# controller.net
KiCad netlist of a schematic drawn in Altium Designer
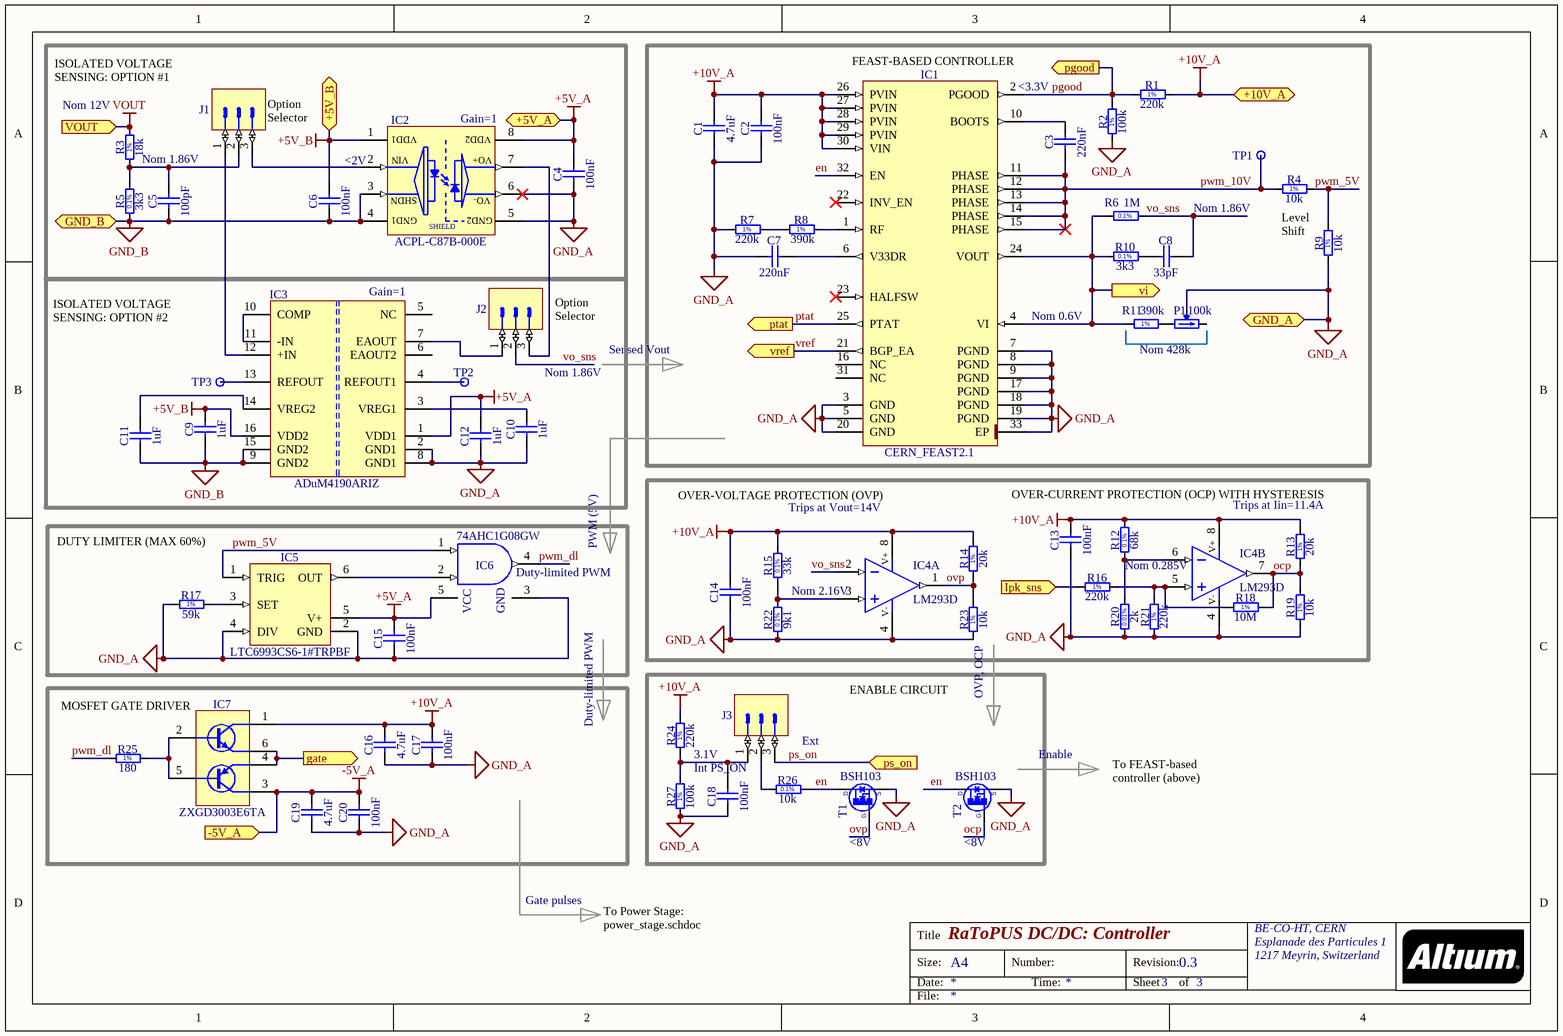
[diagram p0: controller.schdoc]

(export (version "E")
  (design (tool "Eeschema 10.0.6"))
  (components
    (comp (ref "C1")
      (value "4.7uF")
      (footprint "CAPC2012X135N")
      (description "Non-polarised capacitor")
      (fields
        (field (name "PART NUMBER") "CC0805_4.7UF_16V_10%_X7R")
        (field (name "VOLTAGE") "16V")
        (field (name "AUTHOR") "CERN DEM JLC")
      )
      (libsource (lib "Capacitors") (part "Capacitor - non polarized"))
    )
    (comp (ref "C2")
      (value "100nF")
      (footprint "CAPC2012X135N")
      (description "Non-polarised capacitor")
      (fields
        (field (name "PART NUMBER") "CC0805_100NF_50V_10%_X7R")
        (field (name "VOLTAGE") "50V")
        (field (name "AUTHOR") "CERN DEM JLC")
      )
      (libsource (lib "Capacitors") (part "Capacitor - non polarized"))
    )
    (comp (ref "C3")
      (value "220nF")
      (footprint "CAPC2012X135N")
      (description "Non-polarised capacitor")
      (fields
        (field (name "PART NUMBER") "CC0805_220NF_50V_10%_X7R")
        (field (name "VOLTAGE") "50V")
        (field (name "AUTHOR") "CERN DEM JLC")
      )
      (libsource (lib "Capacitors") (part "Capacitor - non polarized"))
    )
    (comp (ref "C4")
      (value "100nF")
      (footprint "CAPC2012X135N")
      (description "Non-polarised capacitor")
      (fields
        (field (name "PART NUMBER") "CC0805_100NF_50V_10%_X7R")
        (field (name "VOLTAGE") "50V")
        (field (name "AUTHOR") "CERN DEM JLC")
      )
      (libsource (lib "Capacitors") (part "Capacitor - non polarized"))
    )
    (comp (ref "C5")
      (value "100pF")
      (footprint "CAPC2012X88N")
      (description "Non-polarised capacitor")
      (fields
        (field (name "PART NUMBER") "CC0805_100PF_50V_5%_C0G_KEMET_C0805C101J5GACAUTO")
        (field (name "VOLTAGE") "50V")
        (field (name "AUTHOR") "CERN DEM BC")
      )
      (libsource (lib "Capacitors") (part "Capacitor - non polarized"))
    )
    (comp (ref "C6")
      (value "100nF")
      (footprint "CAPC2012X135N")
      (description "Non-polarised capacitor")
      (fields
        (field (name "PART NUMBER") "CC0805_100NF_50V_10%_X7R")
        (field (name "VOLTAGE") "50V")
        (field (name "AUTHOR") "CERN DEM JLC")
      )
      (libsource (lib "Capacitors") (part "Capacitor - non polarized"))
    )
    (comp (ref "C7")
      (value "220nF")
      (footprint "CAPC2012X135N")
      (description "Non-polarised capacitor")
      (fields
        (field (name "PART NUMBER") "CC0805_220NF_50V_10%_X7R")
        (field (name "VOLTAGE") "50V")
        (field (name "AUTHOR") "CERN DEM JLC")
      )
      (libsource (lib "Capacitors") (part "Capacitor - non polarized"))
    )
    (comp (ref "C8")
      (value "33pF")
      (footprint "CAPC2012X88N")
      (description "Non-polarised capacitor")
      (fields
        (field (name "PART NUMBER") "CC0805_33PF_50V_5%_C0G_KEMET_C0805C330J5GACAUTO")
        (field (name "VOLTAGE") "50V")
        (field (name "AUTHOR") "CERN DEM BC")
      )
      (libsource (lib "Capacitors") (part "Capacitor - non polarized"))
    )
    (comp (ref "C9")
      (value "1uF")
      (footprint "CAPC3216X140N")
      (description "Non-polarised capacitor")
      (fields
        (field (name "PART NUMBER") "CC1206_1UF_50V_10%_X7R")
        (field (name "VOLTAGE") "50V")
        (field (name "AUTHOR") "CERN DEM JLC")
      )
      (libsource (lib "Capacitors") (part "Capacitor - non polarized"))
    )
    (comp (ref "C10")
      (value "1uF")
      (footprint "CAPC3216X140N")
      (description "Non-polarised capacitor")
      (fields
        (field (name "PART NUMBER") "CC1206_1UF_50V_10%_X7R")
        (field (name "VOLTAGE") "50V")
        (field (name "AUTHOR") "CERN DEM JLC")
      )
      (libsource (lib "Capacitors") (part "Capacitor - non polarized"))
    )
    (comp (ref "C11")
      (value "1uF")
      (footprint "CAPC3216X140N")
      (description "Non-polarised capacitor")
      (fields
        (field (name "PART NUMBER") "CC1206_1UF_50V_10%_X7R")
        (field (name "VOLTAGE") "50V")
        (field (name "AUTHOR") "CERN DEM JLC")
      )
      (libsource (lib "Capacitors") (part "Capacitor - non polarized"))
    )
    (comp (ref "C12")
      (value "1uF")
      (footprint "CAPC3216X140N")
      (description "Non-polarised capacitor")
      (fields
        (field (name "PART NUMBER") "CC1206_1UF_50V_10%_X7R")
        (field (name "VOLTAGE") "50V")
        (field (name "AUTHOR") "CERN DEM JLC")
      )
      (libsource (lib "Capacitors") (part "Capacitor - non polarized"))
    )
    (comp (ref "C13")
      (value "100nF")
      (footprint "CAPC2012X135N")
      (description "Non-polarised capacitor")
      (fields
        (field (name "PART NUMBER") "CC0805_100NF_50V_10%_X7R")
        (field (name "VOLTAGE") "50V")
        (field (name "AUTHOR") "CERN DEM JLC")
      )
      (libsource (lib "Capacitors") (part "Capacitor - non polarized"))
    )
    (comp (ref "C14")
      (value "100nF")
      (footprint "CAPC2012X135N")
      (description "Non-polarised capacitor")
      (fields
        (field (name "PART NUMBER") "CC0805_100NF_50V_10%_X7R")
        (field (name "VOLTAGE") "50V")
        (field (name "AUTHOR") "CERN DEM JLC")
      )
      (libsource (lib "Capacitors") (part "Capacitor - non polarized"))
    )
    (comp (ref "C15")
      (value "100nF")
      (footprint "CAPC2012X135N")
      (description "Non-polarised capacitor")
      (fields
        (field (name "PART NUMBER") "CC0805_100NF_50V_10%_X7R")
        (field (name "VOLTAGE") "50V")
        (field (name "AUTHOR") "CERN DEM JLC")
      )
      (libsource (lib "Capacitors") (part "Capacitor - non polarized"))
    )
    (comp (ref "C16")
      (value "4.7uF")
      (footprint "CAPC2012X135N")
      (description "Non-polarised capacitor")
      (fields
        (field (name "PART NUMBER") "CC0805_4.7UF_16V_10%_X7R")
        (field (name "VOLTAGE") "16V")
        (field (name "AUTHOR") "CERN DEM JLC")
      )
      (libsource (lib "Capacitors") (part "Capacitor - non polarized"))
    )
    (comp (ref "C17")
      (value "100nF")
      (footprint "CAPC2012X135N")
      (description "Non-polarised capacitor")
      (fields
        (field (name "PART NUMBER") "CC0805_100NF_50V_10%_X7R")
        (field (name "VOLTAGE") "50V")
        (field (name "AUTHOR") "CERN DEM JLC")
      )
      (libsource (lib "Capacitors") (part "Capacitor - non polarized"))
    )
    (comp (ref "C18")
      (value "100nF")
      (footprint "CAPC2012X135N")
      (description "Non-polarised capacitor")
      (fields
        (field (name "PART NUMBER") "CC0805_100NF_50V_10%_X7R")
        (field (name "VOLTAGE") "50V")
        (field (name "AUTHOR") "CERN DEM JLC")
      )
      (libsource (lib "Capacitors") (part "Capacitor - non polarized"))
    )
    (comp (ref "C19")
      (value "4.7uF")
      (footprint "CAPC2012X135N")
      (description "Non-polarised capacitor")
      (fields
        (field (name "PART NUMBER") "CC0805_4.7UF_16V_10%_X7R")
        (field (name "VOLTAGE") "16V")
        (field (name "AUTHOR") "CERN DEM JLC")
      )
      (libsource (lib "Capacitors") (part "Capacitor - non polarized"))
    )
    (comp (ref "C20")
      (value "100nF")
      (footprint "CAPC2012X135N")
      (description "Non-polarised capacitor")
      (fields
        (field (name "PART NUMBER") "CC0805_100NF_50V_10%_X7R")
        (field (name "VOLTAGE") "50V")
        (field (name "AUTHOR") "CERN DEM JLC")
      )
      (libsource (lib "Capacitors") (part "Capacitor - non polarized"))
    )
    (comp (ref "IC1")
      (value "CERN_FEAST2.1")
      (footprint "CERN_FEAST2.1")
      (description "Radiation tolerant 10W Synchronous Step-Down Buck DC/DC converter")
      (fields
        (field (name "MANUFACTURER") "CERN")
        (field (name "MANUFACTURER PART NUMBER") "FEAST2.1")
        (field (name "AUTHOR") "CERN DEM JLC")
      )
      (libsource (lib "ICs And Semiconductors") (part "CERN_FEAST2.1"))
    )
    (comp (ref "IC2")
      (value "ACPL-C87B-000E")
      (footprint "AVAGO_ACPL-C87B")
      (description "Precision Optically Isolated Voltage Sensor")
      (fields (field (name "MANUFACTURER") "AVAGO TECHNOLOGIES") (field (name "AUTHOR") "CERN DEM JLC"))
      (libsource (lib "ICs And Semiconductors") (part "ACPL-C87B"))
    )
    (comp (ref "IC3")
      (value "ADuM4190ARIZ")
      (footprint "SOIC127P1031X264-16N")
      (description "High Stability Isolated Error Amplifier")
      (fields (field (name "MANUFACTURER") "ANALOG DEVICES") (field (name "AUTHOR") "CERN DEM JLC"))
      (libsource (lib "ICs And Semiconductors") (part "ADuM4190"))
    )
    (comp (ref "IC4")
      (value "LM293D")
      (footprint "SOIC127P600X175-8N")
      (description "Dual Operational Amplifier")
      (fields (field (name "MANUFACTURER") "TEXAS INSTRUMENTS") (field (name "AUTHOR") "CERN DEM JMW"))
      (libsource (lib "ICs And Semiconductors") (part "Operational Amplifier x2 Type1"))
    )
    (comp (ref "IC5")
      (value "LTC6993CS6-1#TRPBF")
      (footprint "SOT95P280X100-6N")
      (description "TimerBlox: Monostable Pulse Generator (One Shot)")
      (fields (field (name "MANUFACTURER") "LINEAR TECHNOLOGY") (field (name "AUTHOR") "CERN DEM JLC"))
      (libsource (lib "ICs And Semiconductors") (part "LTC6993xS6"))
    )
    (comp (ref "IC6")
      (value "74AHC1G08GW")
      (footprint "SOT65P212X110-5N")
      (description "Single 2-Input AND Gate")
      (fields (field (name "MANUFACTURER") "NXP SEMICONDUCTORS") (field (name "AUTHOR") "CERN DEM JLC"))
      (libsource (lib "ICs And Semiconductors") (part "741G08"))
    )
    (comp (ref "IC7")
      (value "ZXGD3003E6TA")
      (footprint "SOT95P285X140-6N")
      (description "40V 5A Gate Driver")
      (fields (field (name "MANUFACTURER") "DIODES INCORPORATED") (field (name "AUTHOR") "CERN DEM JLC"))
      (libsource (lib "ICs And Semiconductors") (part "ZXGD3003E6TA"))
    )
    (comp (ref "J1")
      (value "Header 3")
      (footprint "JST_B3B-XH-A(LF)(SN)")
      (description "Connector 3 Male")
      (fields
        (field (name "PART NUMBER") "JST_B3B-XH-A(LF)(SN)")
        (field (name "MANUFACTURER") "JST (JAPAN SOLDERLESS TERMINALS)")
        (field (name "AUTHOR") "CERN DEM JLC")
      )
      (libsource (lib "Connectors") (part "Connector 3 Male"))
    )
    (comp (ref "J2")
      (value "Header 3")
      (footprint "JST_B3B-XH-A(LF)(SN)")
      (description "Connector 3 Male")
      (fields
        (field (name "PART NUMBER") "JST_B3B-XH-A(LF)(SN)")
        (field (name "MANUFACTURER") "JST (JAPAN SOLDERLESS TERMINALS)")
        (field (name "AUTHOR") "CERN DEM JLC")
      )
      (libsource (lib "Connectors") (part "Connector 3 Male"))
    )
    (comp (ref "J3")
      (value "Header 3")
      (footprint "JST_B3B-XH-A(LF)(SN)")
      (description "Connector 3 Male")
      (fields
        (field (name "PART NUMBER") "JST_B3B-XH-A(LF)(SN)")
        (field (name "MANUFACTURER") "JST (JAPAN SOLDERLESS TERMINALS)")
        (field (name "AUTHOR") "CERN DEM JLC")
      )
      (libsource (lib "Connectors") (part "Connector 3 Male"))
    )
    (comp (ref "P1")
      (value "100k")
      (footprint "TRIM_VISHAY_TSM4YL")
      (description "Trimming Potentiometer")
      (fields
        (field (name "PART NUMBER") "TRIM_11T_100K_VISHAY_TSM4YL104KR05")
        (field (name "POWER") "0.25W")
        (field (name "AUTHOR") "CERN DEM JLC")
      )
      (libsource (lib "Resistors") (part "Trimming Potentiometer"))
    )
    (comp (ref "R1")
      (value "220k")
      (footprint "RESC2012X60N")
      (description "Resistor - 1%")
      (fields
        (field (name "PART NUMBER") "R0805_220K_1%_0.125W_100PPM")
        (field (name "POWER") "0.125W")
        (field (name "AUTHOR") "CERN DEM JLC")
      )
      (libsource (lib "Resistors") (part "Resistor - 1%"))
    )
    (comp (ref "R2")
      (value "100k")
      (footprint "RESC2012X60N")
      (description "Resistor - 1%")
      (fields
        (field (name "PART NUMBER") "R0805_100K_1%_0.125W_100PPM")
        (field (name "POWER") "0.125W")
        (field (name "AUTHOR") "CERN DEM JLC")
      )
      (libsource (lib "Resistors") (part "Resistor - 1%"))
    )
    (comp (ref "R3")
      (value "18k")
      (footprint "RESC2012X60N")
      (description "Resistor - 1%")
      (fields
        (field (name "PART NUMBER") "R0805_18K_1%_0.125W_100PPM")
        (field (name "POWER") "0.125W")
        (field (name "AUTHOR") "CERN DEM JLC")
      )
      (libsource (lib "Resistors") (part "Resistor - 1%"))
    )
    (comp (ref "R4")
      (value "10k")
      (footprint "RESC2012X60N")
      (description "Resistor - 1%")
      (fields
        (field (name "PART NUMBER") "R0805_10K_1%_0.125W_100PPM")
        (field (name "POWER") "0.125W")
        (field (name "AUTHOR") "CERN DEM JLC")
      )
      (libsource (lib "Resistors") (part "Resistor - 1%"))
    )
    (comp (ref "R5")
      (value "3k3")
      (footprint "RESC2012X60N")
      (description "Resistor - 0.1%")
      (fields
        (field (name "PART NUMBER") "R0805_3K3_0.1%_0.125W_25PPM")
        (field (name "POWER") "0.125W")
        (field (name "AUTHOR") "CERN DEM JLC")
      )
      (libsource (lib "Resistors") (part "Resistor - 0.1%"))
    )
    (comp (ref "R6")
      (value "1M")
      (footprint "RESC2012X60N")
      (description "Resistor - 0.1%")
      (fields
        (field (name "PART NUMBER") "R0805_1M_0.1%_0.1W_25PPM")
        (field (name "POWER") "0.1W")
        (field (name "AUTHOR") "CERN DEM JLC")
      )
      (libsource (lib "Resistors") (part "Resistor - 0.1%"))
    )
    (comp (ref "R7")
      (value "220k")
      (footprint "RESC2012X60N")
      (description "Resistor - 1%")
      (fields
        (field (name "PART NUMBER") "R0805_220K_1%_0.125W_100PPM")
        (field (name "POWER") "0.125W")
        (field (name "AUTHOR") "CERN DEM JLC")
      )
      (libsource (lib "Resistors") (part "Resistor - 1%"))
    )
    (comp (ref "R8")
      (value "390k")
      (footprint "RESC2012X60N")
      (description "Resistor - 1%")
      (fields
        (field (name "PART NUMBER") "R0805_390K_1%_0.125W_100PPM")
        (field (name "POWER") "0.125W")
        (field (name "AUTHOR") "CERN DEM JLC")
      )
      (libsource (lib "Resistors") (part "Resistor - 1%"))
    )
    (comp (ref "R9")
      (value "10k")
      (footprint "RESC2012X60N")
      (description "Resistor - 1%")
      (fields
        (field (name "PART NUMBER") "R0805_10K_1%_0.125W_100PPM")
        (field (name "POWER") "0.125W")
        (field (name "AUTHOR") "CERN DEM JLC")
      )
      (libsource (lib "Resistors") (part "Resistor - 1%"))
    )
    (comp (ref "R10")
      (value "3k3")
      (footprint "RESC2012X60N")
      (description "Resistor - 0.1%")
      (fields
        (field (name "PART NUMBER") "R0805_3K3_0.1%_0.125W_25PPM")
        (field (name "POWER") "0.125W")
        (field (name "AUTHOR") "CERN DEM JLC")
      )
      (libsource (lib "Resistors") (part "Resistor - 0.1%"))
    )
    (comp (ref "R11")
      (value "390k")
      (footprint "RESC2012X60N")
      (description "Resistor - 1%")
      (fields
        (field (name "PART NUMBER") "R0805_390K_1%_0.125W_100PPM")
        (field (name "POWER") "0.125W")
        (field (name "AUTHOR") "CERN DEM JLC")
      )
      (libsource (lib "Resistors") (part "Resistor - 1%"))
    )
    (comp (ref "R12")
      (value "68k")
      (footprint "RESC2012X60N")
      (description "Resistor - 0.1%")
      (fields
        (field (name "PART NUMBER") "R0805_68K_0.1%_0.125W_25PPM")
        (field (name "POWER") "0.125W")
        (field (name "AUTHOR") "CERN DEM JLC")
      )
      (libsource (lib "Resistors") (part "Resistor - 0.1%"))
    )
    (comp (ref "R13")
      (value "20k")
      (footprint "RESC2012X60N")
      (description "Resistor - 1%")
      (fields
        (field (name "PART NUMBER") "R0805_20K_1%_0.125W_100PPM")
        (field (name "POWER") "0.125W")
        (field (name "AUTHOR") "CERN DEM JLC")
      )
      (libsource (lib "Resistors") (part "Resistor - 1%"))
    )
    (comp (ref "R14")
      (value "20k")
      (footprint "RESC2012X60N")
      (description "Resistor - 1%")
      (fields
        (field (name "PART NUMBER") "R0805_20K_1%_0.125W_100PPM")
        (field (name "POWER") "0.125W")
        (field (name "AUTHOR") "CERN DEM JLC")
      )
      (libsource (lib "Resistors") (part "Resistor - 1%"))
    )
    (comp (ref "R15")
      (value "33k")
      (footprint "RESC2012X60N")
      (description "Resistor - 0.1%")
      (fields
        (field (name "PART NUMBER") "R0805_33K_0.1%_0.125W_25PPM")
        (field (name "POWER") "0.125W")
        (field (name "AUTHOR") "CERN DEM JLC")
      )
      (libsource (lib "Resistors") (part "Resistor - 0.1%"))
    )
    (comp (ref "R16")
      (value "220k")
      (footprint "RESC2012X60N")
      (description "Resistor - 1%")
      (fields
        (field (name "PART NUMBER") "R0805_220K_1%_0.125W_100PPM")
        (field (name "POWER") "0.125W")
        (field (name "AUTHOR") "CERN DEM JLC")
      )
      (libsource (lib "Resistors") (part "Resistor - 1%"))
    )
    (comp (ref "R17")
      (value "59k")
      (footprint "RESC2012X60N")
      (description "Resistor - 1%")
      (fields
        (field (name "PART NUMBER") "R0805_59K_1%_0.125W_100PPM")
        (field (name "POWER") "0.125W")
        (field (name "AUTHOR") "CERN DEM JLC")
      )
      (libsource (lib "Resistors") (part "Resistor - 1%"))
    )
    (comp (ref "R18")
      (value "10M")
      (footprint "RESC2012X60N")
      (description "Resistor - 1%")
      (fields
        (field (name "PART NUMBER") "R0805_10M_1%_0.125W_100PPM")
        (field (name "POWER") "0.125W")
        (field (name "AUTHOR") "CERN DEM MR")
      )
      (libsource (lib "Resistors") (part "Resistor - 1%"))
    )
    (comp (ref "R19")
      (value "10k")
      (footprint "RESC2012X60N")
      (description "Resistor - 1%")
      (fields
        (field (name "PART NUMBER") "R0805_10K_1%_0.125W_100PPM")
        (field (name "POWER") "0.125W")
        (field (name "AUTHOR") "CERN DEM JLC")
      )
      (libsource (lib "Resistors") (part "Resistor - 1%"))
    )
    (comp (ref "R20")
      (value "2k")
      (footprint "RESC2013X64N")
      (description "Resistor - 0.01%")
      (fields
        (field (name "PART NUMBER") "R0805_2K_0.01%_0.2W_0.2PPM_VISHAY_VSMP")
        (field (name "POWER") "0.2W")
        (field (name "AUTHOR") "CERN DEM JLC")
      )
      (libsource (lib "Resistors") (part "Resistor - 0.01%"))
    )
    (comp (ref "R21")
      (value "220k")
      (footprint "RESC2012X60N")
      (description "Resistor - 1%")
      (fields
        (field (name "PART NUMBER") "R0805_220K_1%_0.125W_100PPM")
        (field (name "POWER") "0.125W")
        (field (name "AUTHOR") "CERN DEM JLC")
      )
      (libsource (lib "Resistors") (part "Resistor - 1%"))
    )
    (comp (ref "R22")
      (value "9k1")
      (footprint "RESC2012X60N")
      (description "Resistor - 0.1%")
      (fields
        (field (name "PART NUMBER") "R0805_9K1_0.1%_0.1W_10PPM")
        (field (name "POWER") "0.1W")
        (field (name "AUTHOR") "CERN DEM JLC")
      )
      (libsource (lib "Resistors") (part "Resistor - 0.1%"))
    )
    (comp (ref "R23")
      (value "10k")
      (footprint "RESC2012X60N")
      (description "Resistor - 1%")
      (fields
        (field (name "PART NUMBER") "R0805_10K_1%_0.125W_100PPM")
        (field (name "POWER") "0.125W")
        (field (name "AUTHOR") "CERN DEM JLC")
      )
      (libsource (lib "Resistors") (part "Resistor - 1%"))
    )
    (comp (ref "R24")
      (value "220k")
      (footprint "RESC2012X60N")
      (description "Resistor - 1%")
      (fields
        (field (name "PART NUMBER") "R0805_220K_1%_0.125W_100PPM")
        (field (name "POWER") "0.125W")
        (field (name "AUTHOR") "CERN DEM JLC")
      )
      (libsource (lib "Resistors") (part "Resistor - 1%"))
    )
    (comp (ref "R25")
      (value "180")
      (footprint "RESC2012X60N")
      (description "Resistor - 1%")
      (fields
        (field (name "PART NUMBER") "R0805_180R_1%_0.125W_100PPM")
        (field (name "POWER") "0.125W")
        (field (name "AUTHOR") "CERN DEM JLC")
      )
      (libsource (lib "Resistors") (part "Resistor - 1%"))
    )
    (comp (ref "R26")
      (value "10k")
      (footprint "RESC2012X60N")
      (description "Resistor - 0.1%")
      (fields
        (field (name "PART NUMBER") "R0805_10K_0.1%_0.1W_10PPM")
        (field (name "POWER") "0.1W")
        (field (name "AUTHOR") "CERN DEM JLC")
      )
      (libsource (lib "Resistors") (part "Resistor - 0.1%"))
    )
    (comp (ref "R27")
      (value "100k")
      (footprint "RESC2012X60N")
      (description "Resistor - 1%")
      (fields
        (field (name "PART NUMBER") "R0805_100K_1%_0.125W_100PPM")
        (field (name "POWER") "0.125W")
        (field (name "AUTHOR") "CERN DEM JLC")
      )
      (libsource (lib "Resistors") (part "Resistor - 1%"))
    )
    (comp (ref "T1")
      (value "BSH103")
      (footprint "SOT95P230X110-3N")
      (description "N-CHANNEL MOSFET WITH DIODE")
      (fields (field (name "MANUFACTURER") "NEXPERIA") (field (name "AUTHOR") "CERN DEM JLC"))
      (libsource (lib "ICs And Semiconductors") (part "N-MOSFET-D 1G 2S 3D"))
    )
    (comp (ref "T2")
      (value "BSH103")
      (footprint "SOT95P230X110-3N")
      (description "N-CHANNEL MOSFET WITH DIODE")
      (fields (field (name "MANUFACTURER") "NEXPERIA") (field (name "AUTHOR") "CERN DEM JLC"))
      (libsource (lib "ICs And Semiconductors") (part "N-MOSFET-D 1G 2S 3D"))
    )
    (comp (ref "TP1")
      (value "Test Point")
      (footprint "VERO_20-2136")
      (fields
        (field (name "PART NUMBER") "VERO_20-2136")
        (field (name "MANUFACTURER") "VERO TECHNOLOGIES")
        (field (name "MANUFACTURER PART NUMBER") "20-2136")
        (field (name "AUTHOR") "CERN DEM JLC")
      )
      (libsource (lib "Connectors") (part "Test Point"))
    )
    (comp (ref "TP2")
      (value "Test Point")
      (footprint "VERO_20-2136")
      (fields
        (field (name "PART NUMBER") "VERO_20-2136")
        (field (name "MANUFACTURER") "VERO TECHNOLOGIES")
        (field (name "MANUFACTURER PART NUMBER") "20-2136")
        (field (name "AUTHOR") "CERN DEM JLC")
      )
      (libsource (lib "Connectors") (part "Test Point"))
    )
    (comp (ref "TP3")
      (value "Test Point")
      (footprint "VERO_20-2136")
      (fields
        (field (name "PART NUMBER") "VERO_20-2136")
        (field (name "MANUFACTURER") "VERO TECHNOLOGIES")
        (field (name "MANUFACTURER PART NUMBER") "20-2136")
        (field (name "AUTHOR") "CERN DEM JLC")
      )
      (libsource (lib "Connectors") (part "Test Point"))
    )
  )
  (nets
    (net (code "1") (name "+5V_A") (class "Default")
      (node (ref "C12") (pin "2") (pinfunction "2_2") (pintype "passive"))
      (node (ref "C15") (pin "2") (pinfunction "2_2") (pintype "passive"))
      (node (ref "C4") (pin "2") (pinfunction "2_2") (pintype "passive"))
      (node (ref "IC2") (pin "8") (pinfunction "VDD2_8") (pintype "power_in"))
      (node (ref "IC3") (pin "1") (pinfunction "VDD1_1") (pintype "power_in"))
      (node (ref "IC5") (pin "5") (pinfunction "V+_5") (pintype "power_in"))
      (node (ref "IC6") (pin "5") (pinfunction "VCC_5") (pintype "power_in"))
    )
    (net (code "2") (name "+5V_B") (class "Default")
      (node (ref "C6") (pin "2") (pinfunction "2_2") (pintype "passive"))
      (node (ref "C9") (pin "2") (pinfunction "2_2") (pintype "passive"))
      (node (ref "IC2") (pin "1") (pinfunction "VDD1_1") (pintype "power_in"))
      (node (ref "IC3") (pin "16") (pinfunction "VDD2_16") (pintype "power_in"))
    )
    (net (code "3") (name "+10V_A") (class "Default")
      (node (ref "C1") (pin "2") (pinfunction "2_2") (pintype "passive"))
      (node (ref "C13") (pin "2") (pinfunction "2_2") (pintype "passive"))
      (node (ref "C14") (pin "2") (pinfunction "2_2") (pintype "passive"))
      (node (ref "C16") (pin "2") (pinfunction "2_2") (pintype "passive"))
      (node (ref "C17") (pin "2") (pinfunction "2_2") (pintype "passive"))
      (node (ref "C2") (pin "2") (pinfunction "2_2") (pintype "passive"))
      (node (ref "IC1") (pin "26") (pinfunction "PVIN_26") (pintype "input"))
      (node (ref "IC1") (pin "27") (pinfunction "PVIN_27") (pintype "input"))
      (node (ref "IC1") (pin "28") (pinfunction "PVIN_28") (pintype "input"))
      (node (ref "IC1") (pin "29") (pinfunction "PVIN_29") (pintype "input"))
      (node (ref "IC1") (pin "30") (pinfunction "VIN_30") (pintype "input"))
      (node (ref "IC4") (pin "8") (pinfunction "V+_8") (pintype "power_in"))
      (node (ref "IC7") (pin "1") (pinfunction "VCC_1") (pintype "passive"))
      (node (ref "R1") (pin "2") (pinfunction "2_2") (pintype "passive"))
      (node (ref "R12") (pin "2") (pinfunction "2_2") (pintype "passive"))
      (node (ref "R13") (pin "2") (pinfunction "2_2") (pintype "passive"))
      (node (ref "R14") (pin "2") (pinfunction "2_2") (pintype "passive"))
      (node (ref "R15") (pin "2") (pinfunction "2_2") (pintype "passive"))
      (node (ref "R24") (pin "2") (pinfunction "2_2") (pintype "passive"))
    )
    (net (code "4") (name "-5V_A") (class "Default")
      (node (ref "C19") (pin "2") (pinfunction "2_2") (pintype "passive"))
      (node (ref "C20") (pin "2") (pinfunction "2_2") (pintype "passive"))
      (node (ref "IC7") (pin "3") (pinfunction "VEE_3") (pintype "passive"))
    )
    (net (code "5") (name "/Ipk_sns") (class "Default")
      (node (ref "R16") (pin "1") (pinfunction "1_1") (pintype "passive"))
    )
    (net (code "6") (name "/en") (class "Default")
      (node (ref "IC1") (pin "32") (pinfunction "EN_32") (pintype "input"))
      (node (ref "R26") (pin "2") (pinfunction "2_2") (pintype "passive"))
      (node (ref "T1") (pin "3") (pinfunction "D_3") (pintype "passive"))
      (node (ref "T2") (pin "3") (pinfunction "D_3") (pintype "passive"))
    )
    (net (code "7") (name "/gate") (class "Default")
      (node (ref "IC7") (pin "4") (pinfunction "SINK_4") (pintype "passive"))
      (node (ref "IC7") (pin "6") (pinfunction "S_6") (pintype "passive"))
    )
    (net (code "8") (name "/ocp") (class "Default")
      (node (ref "IC4") (pin "7") (pinfunction "OUT_7") (pintype "output"))
      (node (ref "R13") (pin "1") (pinfunction "1_1") (pintype "passive"))
      (node (ref "R18") (pin "2") (pinfunction "2_2") (pintype "passive"))
      (node (ref "R19") (pin "2") (pinfunction "2_2") (pintype "passive"))
      (node (ref "T2") (pin "1") (pinfunction "G_1") (pintype "passive"))
    )
    (net (code "9") (name "/ovp") (class "Default")
      (node (ref "IC4") (pin "1") (pinfunction "OUT_1") (pintype "output"))
      (node (ref "R14") (pin "1") (pinfunction "1_1") (pintype "passive"))
      (node (ref "R23") (pin "2") (pinfunction "2_2") (pintype "passive"))
      (node (ref "T1") (pin "1") (pinfunction "G_1") (pintype "passive"))
    )
    (net (code "10") (name "/pgood") (class "Default")
      (node (ref "IC1") (pin "2") (pinfunction "PGOOD_2") (pintype "output"))
      (node (ref "R1") (pin "1") (pinfunction "1_1") (pintype "passive"))
      (node (ref "R2") (pin "2") (pinfunction "2_2") (pintype "passive"))
    )
    (net (code "11") (name "/ps_on") (class "Default")
      (node (ref "J3") (pin "3") (pinfunction "3_3") (pintype "bidirectional"))
    )
    (net (code "12") (name "/ptat") (class "Default")
      (node (ref "IC1") (pin "25") (pinfunction "PTAT_25") (pintype "output"))
    )
    (net (code "13") (name "/pwm_5V") (class "Default")
      (node (ref "IC5") (pin "1") (pinfunction "TRIG_1") (pintype "input"))
      (node (ref "IC6") (pin "1") (pinfunction "B_1") (pintype "input"))
      (node (ref "R4") (pin "2") (pinfunction "2_2") (pintype "passive"))
      (node (ref "R9") (pin "2") (pinfunction "2_2") (pintype "passive"))
    )
    (net (code "14") (name "/pwm_10V") (class "Default")
      (node (ref "C3") (pin "1") (pinfunction "1_1") (pintype "passive"))
      (node (ref "IC1") (pin "11") (pinfunction "PHASE_11") (pintype "output"))
      (node (ref "IC1") (pin "12") (pinfunction "PHASE_12") (pintype "output"))
      (node (ref "IC1") (pin "13") (pinfunction "PHASE_13") (pintype "output"))
      (node (ref "IC1") (pin "14") (pinfunction "PHASE_14") (pintype "output"))
      (node (ref "IC1") (pin "15") (pinfunction "PHASE_15") (pintype "output"))
      (node (ref "R4") (pin "1") (pinfunction "1_1") (pintype "passive"))
      (node (ref "TP1") (pin "1") (pinfunction "1_1") (pintype "bidirectional"))
    )
    (net (code "15") (name "/pwm_dl") (class "Default")
      (node (ref "IC6") (pin "4") (pinfunction "Y_4") (pintype "output"))
      (node (ref "R25") (pin "1") (pinfunction "1_1") (pintype "passive"))
    )
    (net (code "16") (name "/vi") (class "Default")
      (node (ref "IC1") (pin "24") (pinfunction "VOUT_24") (pintype "output"))
      (node (ref "IC1") (pin "4") (pinfunction "VI_4") (pintype "input"))
      (node (ref "R10") (pin "1") (pinfunction "1_1") (pintype "passive"))
      (node (ref "R11") (pin "1") (pinfunction "1_1") (pintype "passive"))
      (node (ref "R6") (pin "1") (pinfunction "1_1") (pintype "passive"))
    )
    (net (code "17") (name "/vo_sns") (class "Default")
      (node (ref "C8") (pin "2") (pinfunction "2_2") (pintype "passive"))
      (node (ref "IC4") (pin "2") (pinfunction "IN-_2") (pintype "input"))
      (node (ref "J2") (pin "2") (pinfunction "2_2") (pintype "bidirectional"))
      (node (ref "R6") (pin "2") (pinfunction "2_2") (pintype "passive"))
    )
    (net (code "18") (name "/vref") (class "Default")
      (node (ref "IC1") (pin "21") (pinfunction "BGP_EA_21") (pintype "output"))
    )
    (net (code "19") (name "GND_A") (class "Default")
      (node (ref "C1") (pin "1") (pinfunction "1_1") (pintype "passive"))
      (node (ref "C10") (pin "1") (pinfunction "1_1") (pintype "passive"))
      (node (ref "C12") (pin "1") (pinfunction "1_1") (pintype "passive"))
      (node (ref "C13") (pin "1") (pinfunction "1_1") (pintype "passive"))
      (node (ref "C14") (pin "1") (pinfunction "1_1") (pintype "passive"))
      (node (ref "C15") (pin "1") (pinfunction "1_1") (pintype "passive"))
      (node (ref "C16") (pin "1") (pinfunction "1_1") (pintype "passive"))
      (node (ref "C17") (pin "1") (pinfunction "1_1") (pintype "passive"))
      (node (ref "C18") (pin "1") (pinfunction "1_1") (pintype "passive"))
      (node (ref "C19") (pin "1") (pinfunction "1_1") (pintype "passive"))
      (node (ref "C2") (pin "1") (pinfunction "1_1") (pintype "passive"))
      (node (ref "C20") (pin "1") (pinfunction "1_1") (pintype "passive"))
      (node (ref "C4") (pin "1") (pinfunction "1_1") (pintype "passive"))
      (node (ref "C7") (pin "1") (pinfunction "1_1") (pintype "passive"))
      (node (ref "IC1") (pin "17") (pinfunction "PGND_17") (pintype "power_in"))
      (node (ref "IC1") (pin "18") (pinfunction "PGND_18") (pintype "power_in"))
      (node (ref "IC1") (pin "19") (pinfunction "PGND_19") (pintype "power_in"))
      (node (ref "IC1") (pin "20") (pinfunction "GND_20") (pintype "power_in"))
      (node (ref "IC1") (pin "3") (pinfunction "GND_3") (pintype "power_in"))
      (node (ref "IC1") (pin "33") (pinfunction "EP_33") (pintype "power_in"))
      (node (ref "IC1") (pin "5") (pinfunction "GND_5") (pintype "power_in"))
      (node (ref "IC1") (pin "7") (pinfunction "PGND_7") (pintype "power_in"))
      (node (ref "IC1") (pin "8") (pinfunction "PGND_8") (pintype "power_in"))
      (node (ref "IC1") (pin "9") (pinfunction "PGND_9") (pintype "power_in"))
      (node (ref "IC2") (pin "5") (pinfunction "GND2_5") (pintype "power_in"))
      (node (ref "IC2") (pin "6") (pinfunction "VOUT-_6") (pintype "output"))
      (node (ref "IC3") (pin "2") (pinfunction "GND1_2") (pintype "power_in"))
      (node (ref "IC3") (pin "8") (pinfunction "GND1_8") (pintype "power_in"))
      (node (ref "IC4") (pin "4") (pinfunction "V-_4") (pintype "power_in"))
      (node (ref "IC5") (pin "2") (pinfunction "GND_2") (pintype "power_in"))
      (node (ref "IC5") (pin "4") (pinfunction "DIV_4") (pintype "input"))
      (node (ref "IC6") (pin "3") (pinfunction "GND_3") (pintype "power_in"))
      (node (ref "P1") (pin "2") (pinfunction "W_2") (pintype "passive"))
      (node (ref "R17") (pin "1") (pinfunction "1_1") (pintype "passive"))
      (node (ref "R19") (pin "1") (pinfunction "1_1") (pintype "passive"))
      (node (ref "R2") (pin "1") (pinfunction "1_1") (pintype "passive"))
      (node (ref "R20") (pin "1") (pinfunction "1_1") (pintype "passive"))
      (node (ref "R21") (pin "1") (pinfunction "1_1") (pintype "passive"))
      (node (ref "R22") (pin "1") (pinfunction "1_1") (pintype "passive"))
      (node (ref "R23") (pin "1") (pinfunction "1_1") (pintype "passive"))
      (node (ref "R27") (pin "1") (pinfunction "1_1") (pintype "passive"))
      (node (ref "R7") (pin "1") (pinfunction "1_1") (pintype "passive"))
      (node (ref "R9") (pin "1") (pinfunction "1_1") (pintype "passive"))
      (node (ref "T1") (pin "2") (pinfunction "S_2") (pintype "passive"))
      (node (ref "T2") (pin "2") (pinfunction "S_2") (pintype "passive"))
    )
    (net (code "20") (name "GND_B") (class "Default")
      (node (ref "C11") (pin "1") (pinfunction "1_1") (pintype "passive"))
      (node (ref "C5") (pin "1") (pinfunction "1_1") (pintype "passive"))
      (node (ref "C6") (pin "1") (pinfunction "1_1") (pintype "passive"))
      (node (ref "C9") (pin "1") (pinfunction "1_1") (pintype "passive"))
      (node (ref "IC2") (pin "3") (pinfunction "SHDN_3") (pintype "input"))
      (node (ref "IC2") (pin "4") (pinfunction "GND1_4") (pintype "power_in"))
      (node (ref "IC3") (pin "15") (pinfunction "GND2_15") (pintype "power_in"))
      (node (ref "IC3") (pin "9") (pinfunction "GND2_9") (pintype "power_in"))
      (node (ref "R5") (pin "1") (pinfunction "1_1") (pintype "passive"))
    )
    (net (code "21") (name "Net-(C5-Pad2)") (class "Default")
      (node (ref "C5") (pin "2") (pinfunction "2_2") (pintype "passive"))
      (node (ref "J1") (pin "2") (pinfunction "2_2") (pintype "bidirectional"))
      (node (ref "R3") (pin "1") (pinfunction "1_1") (pintype "passive"))
      (node (ref "R5") (pin "2") (pinfunction "2_2") (pintype "passive"))
    )
    (net (code "22") (name "Net-(C8-Pad1)") (class "Default")
      (node (ref "C8") (pin "1") (pinfunction "1_1") (pintype "passive"))
      (node (ref "R10") (pin "2") (pinfunction "2_2") (pintype "passive"))
    )
    (net (code "23") (name "Net-(C18-Pad2)") (class "Default")
      (node (ref "C18") (pin "2") (pinfunction "2_2") (pintype "passive"))
      (node (ref "J3") (pin "1") (pinfunction "1_1") (pintype "bidirectional"))
      (node (ref "R24") (pin "1") (pinfunction "1_1") (pintype "passive"))
      (node (ref "R27") (pin "2") (pinfunction "2_2") (pintype "passive"))
    )
    (net (code "24") (name "Net-(IC1-BOOTS)") (class "Default")
      (node (ref "C3") (pin "2") (pinfunction "2_2") (pintype "passive"))
      (node (ref "IC1") (pin "10") (pinfunction "BOOTS_10") (pintype "output"))
    )
    (net (code "25") (name "Net-(IC1-RF)") (class "Default")
      (node (ref "IC1") (pin "1") (pinfunction "RF_1") (pintype "input"))
      (node (ref "R8") (pin "2") (pinfunction "2_2") (pintype "passive"))
    )
    (net (code "26") (name "Net-(IC1-V33DR)") (class "Default")
      (node (ref "C7") (pin "2") (pinfunction "2_2") (pintype "passive"))
      (node (ref "IC1") (pin "6") (pinfunction "V33DR_6") (pintype "output"))
    )
    (net (code "27") (name "Net-(IC2-VIN)") (class "Default")
      (node (ref "IC2") (pin "2") (pinfunction "VIN_2") (pintype "input"))
      (node (ref "J1") (pin "3") (pinfunction "3_3") (pintype "bidirectional"))
    )
    (net (code "28") (name "Net-(IC2-VOUT+)") (class "Default")
      (node (ref "IC2") (pin "7") (pinfunction "VOUT+_7") (pintype "output"))
      (node (ref "J2") (pin "3") (pinfunction "3_3") (pintype "bidirectional"))
    )
    (net (code "29") (name "Net-(IC3-+IN)") (class "Default")
      (node (ref "IC3") (pin "12") (pinfunction "+IN_12") (pintype "power_in"))
      (node (ref "J1") (pin "1") (pinfunction "1_1") (pintype "bidirectional"))
    )
    (net (code "30") (name "Net-(IC3--IN)") (class "Default")
      (node (ref "IC3") (pin "10") (pinfunction "COMP_10") (pintype "power_in"))
      (node (ref "IC3") (pin "11") (pinfunction "-IN_11") (pintype "power_in"))
    )
    (net (code "31") (name "Net-(IC3-EAOUT)") (class "Default")
      (node (ref "IC3") (pin "7") (pinfunction "EAOUT_7") (pintype "power_in"))
      (node (ref "J2") (pin "1") (pinfunction "1_1") (pintype "bidirectional"))
    )
    (net (code "32") (name "Net-(IC3-REFOUT)") (class "Default")
      (node (ref "IC3") (pin "13") (pinfunction "REFOUT_13") (pintype "power_in"))
      (node (ref "TP3") (pin "1") (pinfunction "1_1") (pintype "bidirectional"))
    )
    (net (code "33") (name "Net-(IC3-REFOUT1)") (class "Default")
      (node (ref "IC3") (pin "4") (pinfunction "REFOUT1_4") (pintype "power_in"))
      (node (ref "TP2") (pin "1") (pinfunction "1_1") (pintype "bidirectional"))
    )
    (net (code "34") (name "Net-(IC3-VREG1)") (class "Default")
      (node (ref "C10") (pin "2") (pinfunction "2_2") (pintype "passive"))
      (node (ref "IC3") (pin "3") (pinfunction "VREG1_3") (pintype "power_in"))
    )
    (net (code "35") (name "Net-(IC3-VREG2)") (class "Default")
      (node (ref "C11") (pin "2") (pinfunction "2_2") (pintype "passive"))
      (node (ref "IC3") (pin "14") (pinfunction "VREG2_14") (pintype "power_in"))
    )
    (net (code "36") (name "Net-(IC4A-IN+)") (class "Default")
      (node (ref "IC4") (pin "3") (pinfunction "IN+_3") (pintype "input"))
      (node (ref "R15") (pin "1") (pinfunction "1_1") (pintype "passive"))
      (node (ref "R22") (pin "2") (pinfunction "2_2") (pintype "passive"))
    )
    (net (code "37") (name "Net-(IC4B-IN+)") (class "Default")
      (node (ref "IC4") (pin "5") (pinfunction "IN+_5") (pintype "input"))
      (node (ref "R16") (pin "2") (pinfunction "2_2") (pintype "passive"))
      (node (ref "R18") (pin "1") (pinfunction "1_1") (pintype "passive"))
      (node (ref "R21") (pin "2") (pinfunction "2_2") (pintype "passive"))
    )
    (net (code "38") (name "Net-(IC4B-IN-)") (class "Default")
      (node (ref "IC4") (pin "6") (pinfunction "IN-_6") (pintype "input"))
      (node (ref "R12") (pin "1") (pinfunction "1_1") (pintype "passive"))
      (node (ref "R20") (pin "2") (pinfunction "2_2") (pintype "passive"))
    )
    (net (code "39") (name "Net-(IC5-OUT)") (class "Default")
      (node (ref "IC5") (pin "6") (pinfunction "OUT_6") (pintype "output"))
      (node (ref "IC6") (pin "2") (pinfunction "A_2") (pintype "input"))
    )
    (net (code "40") (name "Net-(IC5-SET)") (class "Default")
      (node (ref "IC5") (pin "3") (pinfunction "SET_3") (pintype "input"))
      (node (ref "R17") (pin "2") (pinfunction "2_2") (pintype "passive"))
    )
    (net (code "41") (name "Net-(IC7-IN1)") (class "Default")
      (node (ref "IC7") (pin "2") (pinfunction "IN1_2") (pintype "passive"))
      (node (ref "IC7") (pin "5") (pinfunction "IN2_5") (pintype "passive"))
      (node (ref "R25") (pin "2") (pinfunction "2_2") (pintype "passive"))
    )
    (net (code "42") (name "Net-(J3-Pad2)") (class "Default")
      (node (ref "J3") (pin "2") (pinfunction "2_2") (pintype "bidirectional"))
      (node (ref "R26") (pin "1") (pinfunction "1_1") (pintype "passive"))
    )
    (net (code "43") (name "Net-(P1-CCW)") (class "Default")
      (node (ref "P1") (pin "1") (pinfunction "CCW_1") (pintype "passive"))
      (node (ref "R11") (pin "2") (pinfunction "2_2") (pintype "passive"))
    )
    (net (code "44") (name "Net-(R7-Pad2)") (class "Default")
      (node (ref "R7") (pin "2") (pinfunction "2_2") (pintype "passive"))
      (node (ref "R8") (pin "1") (pinfunction "1_1") (pintype "passive"))
    )
    (net (code "45") (name "VOUT") (class "Default")
      (node (ref "R3") (pin "2") (pinfunction "2_2") (pintype "passive"))
    )
    (net (code "46") (name "unconnected-(IC1-HALFSW-Pad23)") (class "Default")
      (node (ref "IC1") (pin "23") (pinfunction "HALFSW_23") (pintype "input+no_connect"))
    )
    (net (code "47") (name "unconnected-(IC1-INV_EN-Pad22)") (class "Default")
      (node (ref "IC1") (pin "22") (pinfunction "INV_EN_22") (pintype "input+no_connect"))
    )
    (net (code "48") (name "unconnected-(IC1-NC-Pad16)") (class "Default")
      (node (ref "IC1") (pin "16") (pinfunction "NC_16") (pintype "passive"))
    )
    (net (code "49") (name "unconnected-(IC1-NC-Pad31)") (class "Default")
      (node (ref "IC1") (pin "31") (pinfunction "NC_31") (pintype "passive"))
    )
    (net (code "50") (name "unconnected-(IC3-EAOUT2-Pad6)") (class "Default")
      (node (ref "IC3") (pin "6") (pinfunction "EAOUT2_6") (pintype "power_in"))
    )
    (net (code "51") (name "unconnected-(IC3-NC-Pad5)") (class "Default")
      (node (ref "IC3") (pin "5") (pinfunction "NC_5") (pintype "power_in"))
    )
    (net (code "52") (name "unconnected-(P1-CW-Pad3)") (class "Default")
      (node (ref "P1") (pin "3") (pinfunction "CW_3") (pintype "passive"))
    )
  )
)
